# ST_LINK_V2-1.net
KiCad netlist of a schematic drawn in Altium Designer
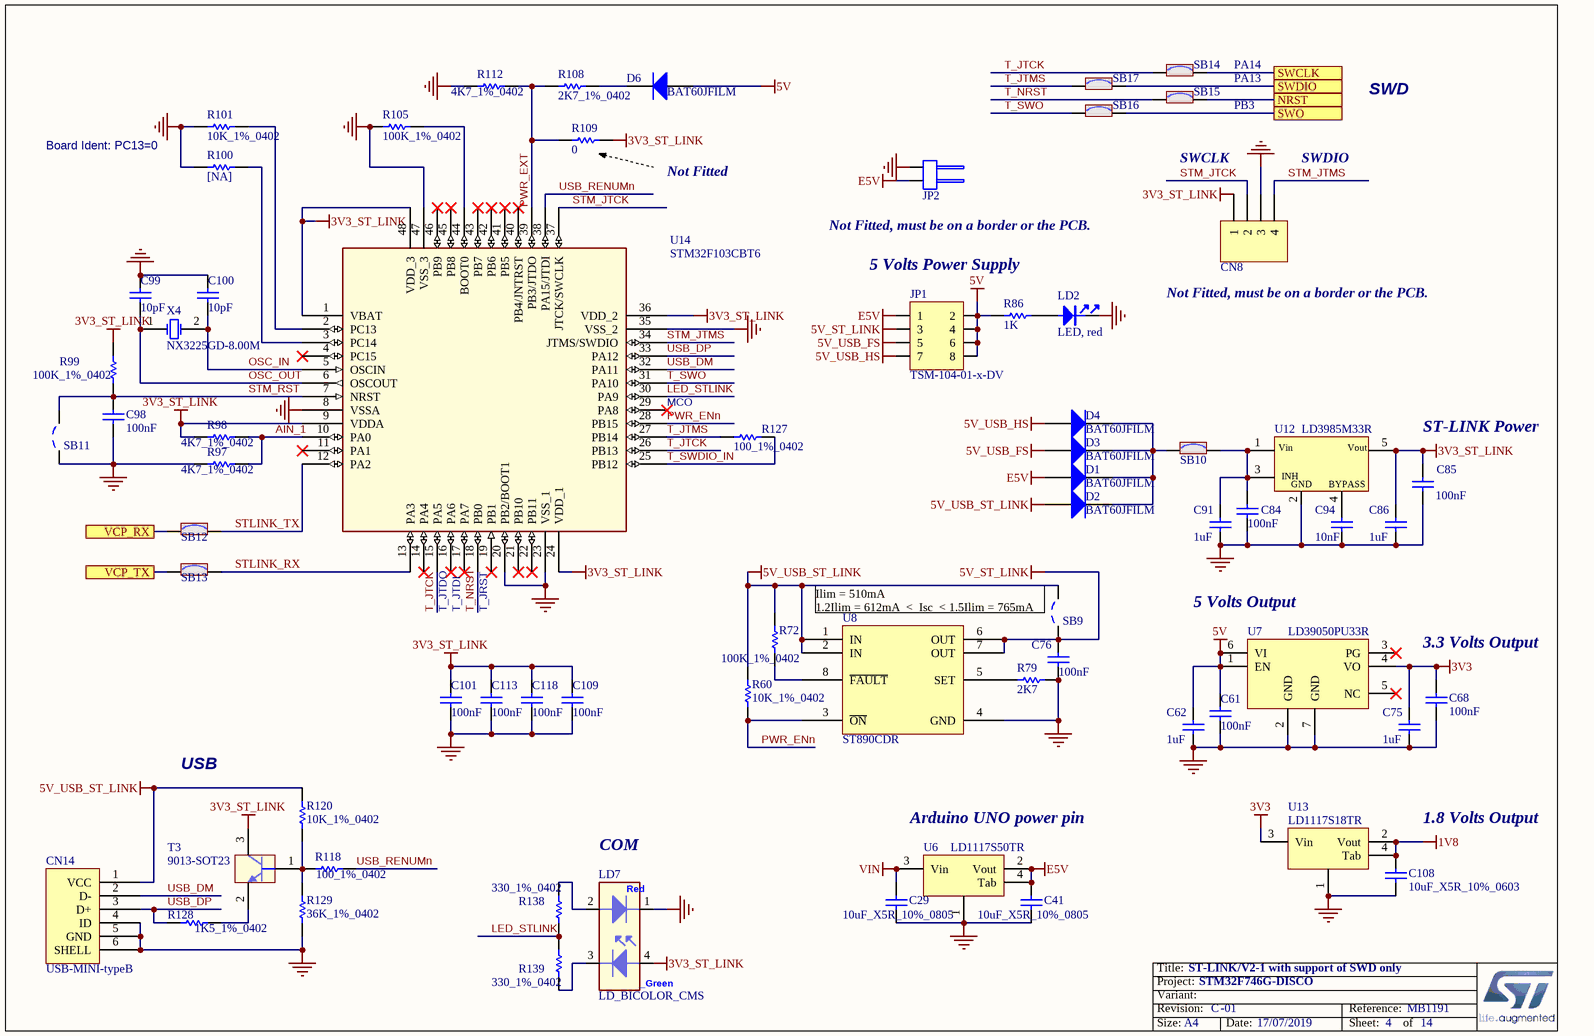
[diagram p0: ST_LINK_V2-1.SCHDOC]

(export (version "E")
  (design (tool "Eeschema 10.0.6"))
  (components
    (comp (ref "C29")
      (value "10uF_X5R_10%_0805")
      (footprint "0805C")
      (description "Capacitor,10uF,25V,X5R,10%,0805,YAGEO")
      (libsource (lib "MCD_TOOLS") (part "Cap_10uF_X5R_10%_0805"))
    )
    (comp (ref "C41")
      (value "10uF_X5R_10%_0805")
      (footprint "0805C")
      (description "Capacitor,10uF,25V,X5R,10%,0805,YAGEO")
      (libsource (lib "MCD_TOOLS") (part "Cap_10uF_X5R_10%_0805"))
    )
    (comp (ref "C61")
      (value "100nF")
      (footprint "0402C")
      (description "Capacitor,100nF,16V,X7R,10%,0402,YAGEO")
      (libsource (lib "MCD_TOOLS") (part "Cap_100nF_X7R_10%_0402"))
    )
    (comp (ref "C62")
      (value "1uF")
      (footprint "0603C")
      (description "Capacitor,1uF,16V,X5R,10%,0603,YAGEO")
      (libsource (lib "MCD_TOOLS") (part "Cap_1uF_X5R_10%_0603"))
    )
    (comp (ref "C68")
      (value "100nF")
      (footprint "0402C")
      (description "Capacitor,100nF,16V,X7R,10%,0402,YAGEO")
      (libsource (lib "MCD_TOOLS") (part "Cap_100nF_X7R_10%_0402"))
    )
    (comp (ref "C75")
      (value "1uF")
      (footprint "0603C")
      (description "Capacitor,1uF,16V,X5R,10%,0603,YAGEO")
      (libsource (lib "MCD_TOOLS") (part "Cap_1uF_X5R_10%_0603"))
    )
    (comp (ref "C76")
      (value "100nF")
      (footprint "0402C")
      (description "Capacitor,100nF,16V,X7R,10%,0402,YAGEO")
      (libsource (lib "MCD_TOOLS") (part "Cap_100nF_X7R_10%_0402"))
    )
    (comp (ref "C84")
      (value "100nF")
      (footprint "0402C")
      (description "Capacitor,100nF,16V,X7R,10%,0402,YAGEO")
      (libsource (lib "MCD_TOOLS") (part "Cap_100nF_X7R_10%_0402"))
    )
    (comp (ref "C85")
      (value "100nF")
      (footprint "0402C")
      (description "Capacitor,100nF,16V,X7R,10%,0402,YAGEO")
      (libsource (lib "MCD_TOOLS") (part "Cap_100nF_X7R_10%_0402"))
    )
    (comp (ref "C86")
      (value "1uF")
      (footprint "0603C")
      (description "Capacitor,1uF,16V,X5R,10%,0603,YAGEO")
      (libsource (lib "MCD_TOOLS") (part "Cap_1uF_X5R_10%_0603"))
    )
    (comp (ref "C91")
      (value "1uF")
      (footprint "0603C")
      (description "Capacitor,1uF,16V,X5R,10%,0603,YAGEO")
      (libsource (lib "MCD_TOOLS") (part "Cap_1uF_X5R_10%_0603"))
    )
    (comp (ref "C94")
      (value "10nF")
      (footprint "0603C")
      (description "Capacitor,10nF,50V,X7R,10%,0603,YAGEO")
      (libsource (lib "MCD_TOOLS") (part "Cap_10nF_X7R_10%_0603"))
    )
    (comp (ref "C98")
      (value "100nF")
      (footprint "0402C")
      (description "Capacitor,100nF,16V,X7R,10%,0402,YAGEO")
      (libsource (lib "MCD_TOOLS") (part "Cap_100nF_X7R_10%_0402"))
    )
    (comp (ref "C99")
      (value "10pF")
      (footprint "0402C")
      (description "Capacitor,10pF,50V,NPO,5%,0402,YAGEO")
      (libsource (lib "MCD_TOOLS") (part "Cap_10pF_NPO_5%_0402"))
    )
    (comp (ref "C100")
      (value "10pF")
      (footprint "0402C")
      (description "Capacitor,10pF,50V,NPO,5%,0402,YAGEO")
      (libsource (lib "MCD_TOOLS") (part "Cap_10pF_NPO_5%_0402"))
    )
    (comp (ref "C101")
      (value "100nF")
      (footprint "0402C")
      (description "Capacitor,100nF,16V,X7R,10%,0402,YAGEO")
      (libsource (lib "MCD_TOOLS") (part "Cap_100nF_X7R_10%_0402"))
    )
    (comp (ref "C108")
      (value "10uF_X5R_10%_0603")
      (footprint "0603C")
      (description "Capacitor,10uF,6.3V,X5R,10%,0603,YAGEO")
      (libsource (lib "MCD_TOOLS") (part "Cap_10uF_X5R_10%_0603"))
    )
    (comp (ref "C109")
      (value "100nF")
      (footprint "0402C")
      (description "Capacitor,100nF,16V,X7R,10%,0402,YAGEO")
      (libsource (lib "MCD_TOOLS") (part "Cap_100nF_X7R_10%_0402"))
    )
    (comp (ref "C113")
      (value "100nF")
      (footprint "0402C")
      (description "Capacitor,100nF,16V,X7R,10%,0402,YAGEO")
      (libsource (lib "MCD_TOOLS") (part "Cap_100nF_X7R_10%_0402"))
    )
    (comp (ref "C118")
      (value "100nF")
      (footprint "0402C")
      (description "Capacitor,100nF,16V,X7R,10%,0402,YAGEO")
      (libsource (lib "MCD_TOOLS") (part "Cap_100nF_X7R_10%_0402"))
    )
    (comp (ref "CN8")
      (value "Header 4")
      (footprint "Header 4")
      (description "Header, 4-Pin")
      (fields (field (name "PUBLISHER") "Altium Limited"))
      (libsource (lib "MCD_TOOLS") (part "Header 4"))
    )
    (comp (ref "CN14")
      (value "USB-MINI-typeB")
      (footprint "USB-MINI-B-SMD")
      (description "USB-MINI-typeB connector")
      (libsource (lib "MCD_TOOLS") (part "USB-MINI-typeB connector"))
    )
    (comp (ref "D1")
      (value "BAT60JFILM")
      (footprint "SOD323/A")
      (libsource (lib "MCD_TOOLS") (part "BAT60JFILM"))
    )
    (comp (ref "D2")
      (value "BAT60JFILM")
      (footprint "SOD323/A")
      (libsource (lib "MCD_TOOLS") (part "BAT60JFILM"))
    )
    (comp (ref "D3")
      (value "BAT60JFILM")
      (footprint "SOD323/A")
      (libsource (lib "MCD_TOOLS") (part "BAT60JFILM"))
    )
    (comp (ref "D4")
      (value "BAT60JFILM")
      (footprint "SOD323/A")
      (libsource (lib "MCD_TOOLS") (part "BAT60JFILM"))
    )
    (comp (ref "D6")
      (value "BAT60JFILM")
      (footprint "SOD323/A")
      (libsource (lib "MCD_TOOLS") (part "BAT60JFILM"))
    )
    (comp (ref "JP1")
      (value "TSM-104-01-x-DV")
      (footprint "TSM-104-01-x-DV")
      (description "Header, 4-Pins, Double row Vertical, SMD, 2.54")
      (libsource (lib "MCD_TOOLS") (part "Header_4X2_SMD"))
    )
    (comp (ref "JP2")
      (value "TSM-102-01-F-SH-A")
      (footprint "TSM-102-01-F-SH-A")
      (description "Header, 2-Pins, Single row Horizontal SMD, 2.54")
      (libsource (lib "MCD_TOOLS") (part "JP2_CMS"))
    )
    (comp (ref "LD2")
      (value "LED, red")
      (footprint "0603D")
      (description "LED, red, 0603")
      (libsource (lib "MCD_TOOLS") (part "LED_red"))
    )
    (comp (ref "LD7")
      (value "LD_BICOLOR_CMS")
      (footprint "HSMF-A201")
      (description "Bicolor Led")
      (libsource (lib "MCD_TOOLS") (part "LD_BICOLOR_CMS"))
    )
    (comp (ref "R60")
      (value "10K_1%_0402")
      (footprint "0402R")
      (description "Resistor,10K,0402,1%,YAGEO")
      (libsource (lib "MCD_TOOLS") (part "Res_10K_1%_0402"))
    )
    (comp (ref "R72")
      (value "100K_1%_0402")
      (footprint "0402R")
      (description "Resistor,100K,0402,1%,YAGEO")
      (libsource (lib "MCD_TOOLS") (part "Res_100K_1%_0402"))
    )
    (comp (ref "R79")
      (value "2K7")
      (footprint "0402R")
      (description "Resistor,2K7,0402,1%,YAGEO")
      (libsource (lib "MCD_TOOLS") (part "Res_2K7_1%_0402"))
    )
    (comp (ref "R86")
      (value "1K")
      (footprint "0402R")
      (description "Resistor,1K,0402,1%,YAGEO")
      (libsource (lib "MCD_TOOLS") (part "Res_1K_1%_0402"))
    )
    (comp (ref "R97")
      (value "4K7_1%_0402")
      (footprint "0402R")
      (description "Resistor,4K7,0402,1%,YAGEO")
      (libsource (lib "MCD_TOOLS") (part "Res_4K7_1%_0402"))
    )
    (comp (ref "R98")
      (value "4K7_1%_0402")
      (footprint "0402R")
      (description "Resistor,4K7,0402,1%,YAGEO")
      (libsource (lib "MCD_TOOLS") (part "Res_4K7_1%_0402"))
    )
    (comp (ref "R99")
      (value "100K_1%_0402")
      (footprint "0402R")
      (description "Resistor,100K,0402,1%,YAGEO")
      (libsource (lib "MCD_TOOLS") (part "Res_100K_1%_0402"))
    )
    (comp (ref "R100")
      (value "[NA]")
      (footprint "0402R")
      (description "Resistor,[NA],0402")
      (libsource (lib "MCD_TOOLS") (part "Res_NA_0402"))
    )
    (comp (ref "R101")
      (value "10K_1%_0402")
      (footprint "0402R")
      (description "Resistor,10K,0402,1%,YAGEO")
      (libsource (lib "MCD_TOOLS") (part "Res_10K_1%_0402"))
    )
    (comp (ref "R105")
      (value "100K_1%_0402")
      (footprint "0402R")
      (description "Resistor,100K,0402,1%,YAGEO")
      (libsource (lib "MCD_TOOLS") (part "Res_100K_1%_0402"))
    )
    (comp (ref "R108")
      (value "2K7_1%_0402")
      (footprint "0402R")
      (description "Resistor,2K7,0402,1%,YAGEO")
      (libsource (lib "MCD_TOOLS") (part "Res_2K7_1%_0402"))
    )
    (comp (ref "R109")
      (value "0")
      (footprint "0402R")
      (description "Resistor,0,0402,5%,YAGEO")
      (libsource (lib "MCD_TOOLS") (part "Res_0_5%_0402"))
    )
    (comp (ref "R112")
      (value "4K7_1%_0402")
      (footprint "0402R")
      (description "Resistor,4K7,0402,1%,YAGEO")
      (libsource (lib "MCD_TOOLS") (part "Res_4K7_1%_0402"))
    )
    (comp (ref "R118")
      (value "100_1%_0402")
      (footprint "0402R")
      (description "Resistor,100,0402,1%,YAGEO")
      (libsource (lib "MCD_TOOLS") (part "Res_100_1%_0402"))
    )
    (comp (ref "R120")
      (value "10K_1%_0402")
      (footprint "0402R")
      (description "Resistor,10K,0402,1%,YAGEO")
      (libsource (lib "MCD_TOOLS") (part "Res_10K_1%_0402"))
    )
    (comp (ref "R127")
      (value "100_1%_0402")
      (footprint "0402R")
      (description "Resistor,100,0402,1%,YAGEO")
      (libsource (lib "MCD_TOOLS") (part "Res_100_1%_0402"))
    )
    (comp (ref "R128")
      (value "1K5_1%_0402")
      (footprint "0402R")
      (description "Resistor,1K5,0402,1%,YAGEO")
      (libsource (lib "MCD_TOOLS") (part "Res_1K5_1%_0402"))
    )
    (comp (ref "R129")
      (value "36K_1%_0402")
      (footprint "0402R")
      (description "Resistor,36K,0402,1%,YAGEO")
      (libsource (lib "MCD_TOOLS") (part "Res_36K_1%_0402"))
    )
    (comp (ref "R138")
      (value "330_1%_0402")
      (footprint "0402R")
      (description "Resistor,330,0402,1%,YAGEO")
      (libsource (lib "MCD_TOOLS") (part "Res_330_1%_0402"))
    )
    (comp (ref "R139")
      (value "330_1%_0402")
      (footprint "0402R")
      (description "Resistor,330,0402,1%,YAGEO")
      (libsource (lib "MCD_TOOLS") (part "Res_330_1%_0402"))
    )
    (comp (ref "SB9")
      (value "Solder Bridge OFF")
      (footprint "JP2_SMD")
      (libsource (lib "MCD_TOOLS") (part "SB_OFF"))
    )
    (comp (ref "SB10")
      (value "Solder Bridge ON")
      (footprint "JP2_SMD")
      (libsource (lib "MCD_TOOLS") (part "SB_ON"))
    )
    (comp (ref "SB11")
      (value "Solder Bridge OFF")
      (footprint "JP2_SMD")
      (libsource (lib "MCD_TOOLS") (part "SB_OFF"))
    )
    (comp (ref "SB12")
      (value "Solder Bridge ON")
      (footprint "JP2_SMD")
      (libsource (lib "MCD_TOOLS") (part "SB_ON"))
    )
    (comp (ref "SB13")
      (value "Solder Bridge ON")
      (footprint "JP2_SMD")
      (libsource (lib "MCD_TOOLS") (part "SB_ON"))
    )
    (comp (ref "SB14")
      (value "Solder Bridge ON")
      (footprint "JP2_SMD")
      (libsource (lib "MCD_TOOLS") (part "SB_ON"))
    )
    (comp (ref "SB15")
      (value "Solder Bridge ON")
      (footprint "JP2_SMD")
      (libsource (lib "MCD_TOOLS") (part "SB_ON"))
    )
    (comp (ref "SB16")
      (value "Solder Bridge ON")
      (footprint "JP2_SMD")
      (libsource (lib "MCD_TOOLS") (part "SB_ON"))
    )
    (comp (ref "SB17")
      (value "Solder Bridge ON")
      (footprint "JP2_SMD")
      (libsource (lib "MCD_TOOLS") (part "SB_ON"))
    )
    (comp (ref "T3")
      (value "9013-SOT23")
      (footprint "SOT23")
      (description "NPN Bipolar Transistor")
      (libsource (lib "MCD_TOOLS") (part "9013-SOT23"))
    )
    (comp (ref "U6")
      (value "LD1117S50TR")
      (footprint "SOT-223")
      (description "IC REG LDO 5V 0.8A SOT223")
      (libsource (lib "MCD_TOOLS") (part "LD1117S50TR"))
    )
    (comp (ref "U7")
      (value "LD39050PU33R")
      (footprint "DFN6_3x3")
      (description "Ultra low drop-low , 500 mA low quiescent current")
      (libsource (lib "MCD_TOOLS") (part "LD39050P"))
    )
    (comp (ref "U8")
      (value "ST890CDR")
      (footprint "SO-8")
      (description "1.2 A current limited high-side power switch with thermal shutdown")
      (libsource (lib "MCD_TOOLS") (part "ST890CDR"))
    )
    (comp (ref "U12")
      (value "LD3985M33R")
      (footprint "SOT23-5L")
      (description "Ultra low drop-low noise BiCMOS voltage, regulators low ESR capacitors compatible")
      (libsource (lib "MCD_TOOLS") (part "LD3985M33R"))
    )
    (comp (ref "U13")
      (value "LD1117S18TR")
      (footprint "SOT-223")
      (description "LOW DROP FIXED AND ADJUSTABLE POSITIVE VOLTAGE REGULATORS (1.8 Volts)")
      (libsource (lib "MCD_TOOLS") (part "LD1117S18TR"))
    )
    (comp (ref "U14")
      (value "STM32F103CBT6")
      (footprint "QFP48 7x7")
      (description "Medium-density performance line ARM-based 32-bit MCU with 128KB Flash")
      (libsource (lib "MCD_TOOLS") (part "STM32F103CBT6"))
    )
    (comp (ref "X4")
      (value "NX3225GD-8.00M")
      (footprint "XTAL_2SM_3R2X2R5")
      (description "Crystal 8Mhz, 8pF, -+50PPM, SMD")
      (libsource (lib "MCD_TOOLS") (part "XTAL_8M_NX3225GD"))
    )
  )
  (nets
    (net (code "1") (name "/AIN_1") (class "Default")
      (node (ref "R97") (pin "2") (pinfunction "2_2") (pintype "passive"))
      (node (ref "R98") (pin "2") (pinfunction "2_2") (pintype "passive"))
      (node (ref "U14") (pin "10") (pinfunction "PA0_10") (pintype "bidirectional"))
    )
    (net (code "2") (name "/LED_STLINK") (class "Default")
      (node (ref "R138") (pin "1") (pinfunction "1_1") (pintype "passive"))
      (node (ref "R139") (pin "2") (pinfunction "2_2") (pintype "passive"))
      (node (ref "U14") (pin "30") (pinfunction "PA9_30") (pintype "bidirectional"))
    )
    (net (code "3") (name "/NRST") (class "Default")
      (node (ref "SB15") (pin "2") (pinfunction "2_2") (pintype "passive"))
    )
    (net (code "4") (name "/OSC_IN") (class "Default")
      (node (ref "C100") (pin "2") (pinfunction "2_2") (pintype "passive"))
      (node (ref "U14") (pin "5") (pinfunction "OSCIN_5") (pintype "input"))
      (node (ref "X4") (pin "2") (pinfunction "OSC2_2") (pintype "passive"))
    )
    (net (code "5") (name "/OSC_OUT") (class "Default")
      (node (ref "C99") (pin "2") (pinfunction "2_2") (pintype "passive"))
      (node (ref "U14") (pin "6") (pinfunction "OSCOUT_6") (pintype "output"))
      (node (ref "X4") (pin "1") (pinfunction "OSC1_1") (pintype "passive"))
    )
    (net (code "6") (name "/PWR_ENn") (class "Default")
      (node (ref "R60") (pin "1") (pinfunction "1_1") (pintype "passive"))
      (node (ref "U14") (pin "28") (pinfunction "PB15_28") (pintype "bidirectional"))
      (node (ref "U8") (pin "3") (pinfunction "~{ON}_3") (pintype "passive"))
    )
    (net (code "7") (name "/PWR_EXT") (class "Default")
      (node (ref "R108") (pin "1") (pinfunction "1_1") (pintype "passive"))
      (node (ref "R109") (pin "1") (pinfunction "1_1") (pintype "passive"))
      (node (ref "R112") (pin "2") (pinfunction "2_2") (pintype "passive"))
      (node (ref "U14") (pin "39") (pinfunction "PB3/JTDO_39") (pintype "bidirectional"))
    )
    (net (code "8") (name "/STLINK_RX") (class "Default")
      (node (ref "SB13") (pin "2") (pinfunction "2_2") (pintype "passive"))
      (node (ref "U14") (pin "13") (pinfunction "PA3_13") (pintype "bidirectional"))
    )
    (net (code "9") (name "/STLINK_TX") (class "Default")
      (node (ref "SB12") (pin "2") (pinfunction "2_2") (pintype "passive"))
      (node (ref "U14") (pin "12") (pinfunction "PA2_12") (pintype "bidirectional"))
    )
    (net (code "10") (name "/STM_JTCK") (class "Default")
      (node (ref "CN8") (pin "2") (pinfunction "2_2") (pintype "passive"))
      (node (ref "U14") (pin "37") (pinfunction "JTCK/SWCLK_37") (pintype "bidirectional"))
    )
    (net (code "11") (name "/STM_JTMS") (class "Default")
      (node (ref "CN8") (pin "4") (pinfunction "4_4") (pintype "passive"))
      (node (ref "U14") (pin "34") (pinfunction "JTMS/SWDIO_34") (pintype "bidirectional"))
    )
    (net (code "12") (name "/STM_RST") (class "Default")
      (node (ref "C98") (pin "2") (pinfunction "2_2") (pintype "passive"))
      (node (ref "R99") (pin "1") (pinfunction "1_1") (pintype "passive"))
      (node (ref "SB11") (pin "2") (pinfunction "2_2") (pintype "passive"))
      (node (ref "U14") (pin "7") (pinfunction "NRST_7") (pintype "input"))
    )
    (net (code "13") (name "/SWCLK") (class "Default")
      (node (ref "SB14") (pin "2") (pinfunction "2_2") (pintype "passive"))
    )
    (net (code "14") (name "/SWDIO") (class "Default")
      (node (ref "SB17") (pin "2") (pinfunction "2_2") (pintype "passive"))
    )
    (net (code "15") (name "/SWO") (class "Default")
      (node (ref "SB16") (pin "2") (pinfunction "2_2") (pintype "passive"))
    )
    (net (code "16") (name "/T_JTCK") (class "Default")
      (node (ref "SB14") (pin "1") (pinfunction "1_1") (pintype "passive"))
      (node (ref "U14") (pin "15") (pinfunction "PA5_15") (pintype "bidirectional"))
      (node (ref "U14") (pin "26") (pinfunction "PB13_26") (pintype "bidirectional"))
    )
    (net (code "17") (name "/T_JTMS") (class "Default")
      (node (ref "R127") (pin "1") (pinfunction "1_1") (pintype "passive"))
      (node (ref "SB17") (pin "1") (pinfunction "1_1") (pintype "passive"))
      (node (ref "U14") (pin "27") (pinfunction "PB14_27") (pintype "bidirectional"))
    )
    (net (code "18") (name "/T_NRST") (class "Default")
      (node (ref "SB15") (pin "1") (pinfunction "1_1") (pintype "passive"))
      (node (ref "U14") (pin "18") (pinfunction "PB0_18") (pintype "bidirectional"))
    )
    (net (code "19") (name "/T_SWDIO_IN") (class "Default")
      (node (ref "R127") (pin "2") (pinfunction "2_2") (pintype "passive"))
      (node (ref "U14") (pin "25") (pinfunction "PB12_25") (pintype "bidirectional"))
    )
    (net (code "20") (name "/T_SWO") (class "Default")
      (node (ref "SB16") (pin "1") (pinfunction "1_1") (pintype "passive"))
      (node (ref "U14") (pin "31") (pinfunction "PA10_31") (pintype "bidirectional"))
    )
    (net (code "21") (name "/USB_DM") (class "Default")
      (node (ref "CN14") (pin "2") (pinfunction "D-_2") (pintype "passive"))
      (node (ref "U14") (pin "32") (pinfunction "PA11_32") (pintype "bidirectional"))
    )
    (net (code "22") (name "/USB_DP") (class "Default")
      (node (ref "CN14") (pin "3") (pinfunction "D+_3") (pintype "passive"))
      (node (ref "R128") (pin "1") (pinfunction "1_1") (pintype "passive"))
      (node (ref "U14") (pin "33") (pinfunction "PA12_33") (pintype "bidirectional"))
    )
    (net (code "23") (name "/USB_RENUMn") (class "Default")
      (node (ref "R118") (pin "2") (pinfunction "2_2") (pintype "passive"))
      (node (ref "U14") (pin "38") (pinfunction "PA15/JTDI_38") (pintype "bidirectional"))
    )
    (net (code "24") (name "/VCP_RX") (class "Default")
      (node (ref "SB12") (pin "1") (pinfunction "1_1") (pintype "passive"))
    )
    (net (code "25") (name "/VCP_TX") (class "Default")
      (node (ref "SB13") (pin "1") (pinfunction "1_1") (pintype "passive"))
    )
    (net (code "26") (name "1V8") (class "Default")
      (node (ref "C108") (pin "2") (pinfunction "2_2") (pintype "passive"))
      (node (ref "U13") (pin "2") (pinfunction "Vout_2") (pintype "passive"))
      (node (ref "U13") (pin "4") (pinfunction "Tab_4") (pintype "passive"))
    )
    (net (code "27") (name "3V3") (class "Default")
      (node (ref "C68") (pin "2") (pinfunction "2_2") (pintype "passive"))
      (node (ref "C75") (pin "2") (pinfunction "2_2") (pintype "passive"))
      (node (ref "U13") (pin "3") (pinfunction "Vin_3") (pintype "passive"))
      (node (ref "U7") (pin "4") (pinfunction "VO_4") (pintype "passive"))
    )
    (net (code "28") (name "3V3_ST_LINK") (class "Default")
      (node (ref "C101") (pin "2") (pinfunction "2_2") (pintype "passive"))
      (node (ref "C109") (pin "2") (pinfunction "2_2") (pintype "passive"))
      (node (ref "C113") (pin "2") (pinfunction "2_2") (pintype "passive"))
      (node (ref "C118") (pin "1") (pinfunction "1_1") (pintype "passive"))
      (node (ref "C85") (pin "2") (pinfunction "2_2") (pintype "passive"))
      (node (ref "C86") (pin "1") (pinfunction "1_1") (pintype "passive"))
      (node (ref "CN8") (pin "1") (pinfunction "1_1") (pintype "passive"))
      (node (ref "LD7") (pin "4") (pinfunction "4_4") (pintype "passive"))
      (node (ref "R109") (pin "2") (pinfunction "2_2") (pintype "passive"))
      (node (ref "R98") (pin "1") (pinfunction "1_1") (pintype "passive"))
      (node (ref "R99") (pin "2") (pinfunction "2_2") (pintype "passive"))
      (node (ref "T3") (pin "3") (pinfunction "C_3") (pintype "passive"))
      (node (ref "U12") (pin "5") (pinfunction "Vout_5") (pintype "passive"))
      (node (ref "U14") (pin "1") (pinfunction "VBAT_1") (pintype "power_in"))
      (node (ref "U14") (pin "24") (pinfunction "VDD_1_24") (pintype "power_in"))
      (node (ref "U14") (pin "36") (pinfunction "VDD_2_36") (pintype "power_in"))
      (node (ref "U14") (pin "48") (pinfunction "VDD_3_48") (pintype "power_in"))
      (node (ref "U14") (pin "9") (pinfunction "VDDA_9") (pintype "power_in"))
    )
    (net (code "29") (name "5V") (class "Default")
      (node (ref "C61") (pin "2") (pinfunction "2_2") (pintype "passive"))
      (node (ref "C62") (pin "2") (pinfunction "2_2") (pintype "passive"))
      (node (ref "D6") (pin "1") (pinfunction "A_1") (pintype "passive"))
      (node (ref "JP1") (pin "2") (pinfunction "2_2") (pintype "passive"))
      (node (ref "JP1") (pin "4") (pinfunction "4_4") (pintype "passive"))
      (node (ref "JP1") (pin "6") (pinfunction "6_6") (pintype "passive"))
      (node (ref "JP1") (pin "8") (pinfunction "8_8") (pintype "passive"))
      (node (ref "R86") (pin "1") (pinfunction "1_1") (pintype "passive"))
      (node (ref "U7") (pin "1") (pinfunction "EN_1") (pintype "passive"))
      (node (ref "U7") (pin "6") (pinfunction "VI_6") (pintype "passive"))
    )
    (net (code "30") (name "5V_ST_LINK") (class "Default")
      (node (ref "C76") (pin "2") (pinfunction "2_2") (pintype "passive"))
      (node (ref "JP1") (pin "3") (pinfunction "3_3") (pintype "passive"))
      (node (ref "SB9") (pin "1") (pinfunction "1_1") (pintype "passive"))
      (node (ref "U8") (pin "6") (pinfunction "OUT_6") (pintype "passive"))
      (node (ref "U8") (pin "7") (pinfunction "OUT_7") (pintype "passive"))
    )
    (net (code "31") (name "5V_USB_FS") (class "Default")
      (node (ref "D3") (pin "1") (pinfunction "A_1") (pintype "passive"))
      (node (ref "JP1") (pin "5") (pinfunction "5_5") (pintype "passive"))
    )
    (net (code "32") (name "5V_USB_HS") (class "Default")
      (node (ref "D4") (pin "1") (pinfunction "A_1") (pintype "passive"))
      (node (ref "JP1") (pin "7") (pinfunction "7_7") (pintype "passive"))
    )
    (net (code "33") (name "5V_USB_ST_LINK") (class "Default")
      (node (ref "CN14") (pin "1") (pinfunction "VCC_1") (pintype "power_in"))
      (node (ref "D2") (pin "1") (pinfunction "A_1") (pintype "passive"))
      (node (ref "R120") (pin "2") (pinfunction "2_2") (pintype "passive"))
      (node (ref "R60") (pin "2") (pinfunction "2_2") (pintype "passive"))
      (node (ref "R72") (pin "2") (pinfunction "2_2") (pintype "passive"))
      (node (ref "SB9") (pin "2") (pinfunction "2_2") (pintype "passive"))
      (node (ref "U8") (pin "1") (pinfunction "IN_1") (pintype "passive"))
      (node (ref "U8") (pin "2") (pinfunction "IN_2") (pintype "passive"))
    )
    (net (code "34") (name "E5V") (class "Default")
      (node (ref "C41") (pin "2") (pinfunction "2_2") (pintype "passive"))
      (node (ref "D1") (pin "1") (pinfunction "A_1") (pintype "passive"))
      (node (ref "JP1") (pin "1") (pinfunction "1_1") (pintype "passive"))
      (node (ref "JP2") (pin "2") (pinfunction "NO_2") (pintype "passive"))
      (node (ref "U6") (pin "2") (pinfunction "Vout_2") (pintype "passive"))
      (node (ref "U6") (pin "4") (pinfunction "Tab_4") (pintype "passive"))
    )
    (net (code "35") (name "GND") (class "Default")
      (node (ref "C100") (pin "1") (pinfunction "1_1") (pintype "passive"))
      (node (ref "C101") (pin "1") (pinfunction "1_1") (pintype "passive"))
      (node (ref "C108") (pin "1") (pinfunction "1_1") (pintype "passive"))
      (node (ref "C109") (pin "1") (pinfunction "1_1") (pintype "passive"))
      (node (ref "C113") (pin "1") (pinfunction "1_1") (pintype "passive"))
      (node (ref "C118") (pin "2") (pinfunction "2_2") (pintype "passive"))
      (node (ref "C29") (pin "1") (pinfunction "1_1") (pintype "passive"))
      (node (ref "C41") (pin "1") (pinfunction "1_1") (pintype "passive"))
      (node (ref "C61") (pin "1") (pinfunction "1_1") (pintype "passive"))
      (node (ref "C62") (pin "1") (pinfunction "1_1") (pintype "passive"))
      (node (ref "C68") (pin "1") (pinfunction "1_1") (pintype "passive"))
      (node (ref "C75") (pin "1") (pinfunction "1_1") (pintype "passive"))
      (node (ref "C76") (pin "1") (pinfunction "1_1") (pintype "passive"))
      (node (ref "C84") (pin "1") (pinfunction "1_1") (pintype "passive"))
      (node (ref "C85") (pin "1") (pinfunction "1_1") (pintype "passive"))
      (node (ref "C86") (pin "2") (pinfunction "2_2") (pintype "passive"))
      (node (ref "C91") (pin "1") (pinfunction "1_1") (pintype "passive"))
      (node (ref "C94") (pin "1") (pinfunction "1_1") (pintype "passive"))
      (node (ref "C98") (pin "1") (pinfunction "1_1") (pintype "passive"))
      (node (ref "C99") (pin "1") (pinfunction "1_1") (pintype "passive"))
      (node (ref "CN14") (pin "4") (pinfunction "ID_4") (pintype "passive"))
      (node (ref "CN14") (pin "5") (pinfunction "GND_5") (pintype "passive"))
      (node (ref "CN14") (pin "6") (pinfunction "SHELL_6") (pintype "passive"))
      (node (ref "CN8") (pin "3") (pinfunction "3_3") (pintype "passive"))
      (node (ref "JP2") (pin "1") (pinfunction "COMMON_1") (pintype "passive"))
      (node (ref "LD2") (pin "2") (pintype "passive"))
      (node (ref "LD7") (pin "1") (pinfunction "1_1") (pintype "passive"))
      (node (ref "R100") (pin "1") (pinfunction "1_1") (pintype "passive"))
      (node (ref "R101") (pin "1") (pinfunction "1_1") (pintype "passive"))
      (node (ref "R105") (pin "1") (pinfunction "1_1") (pintype "passive"))
      (node (ref "R112") (pin "1") (pinfunction "1_1") (pintype "passive"))
      (node (ref "R129") (pin "1") (pinfunction "1_1") (pintype "passive"))
      (node (ref "R79") (pin "2") (pinfunction "2_2") (pintype "passive"))
      (node (ref "R97") (pin "1") (pinfunction "1_1") (pintype "passive"))
      (node (ref "SB11") (pin "1") (pinfunction "1_1") (pintype "passive"))
      (node (ref "U12") (pin "2") (pinfunction "GND_2") (pintype "passive"))
      (node (ref "U13") (pin "1") (pintype "passive"))
      (node (ref "U14") (pin "20") (pinfunction "PB2/BOOT1_20") (pintype "bidirectional"))
      (node (ref "U14") (pin "23") (pinfunction "VSS_1_23") (pintype "power_in"))
      (node (ref "U14") (pin "35") (pinfunction "VSS_2_35") (pintype "power_in"))
      (node (ref "U14") (pin "47") (pinfunction "VSS_3_47") (pintype "power_in"))
      (node (ref "U14") (pin "8") (pinfunction "VSSA_8") (pintype "power_in"))
      (node (ref "U6") (pin "1") (pintype "passive"))
      (node (ref "U7") (pin "2") (pinfunction "GND_2") (pintype "passive"))
      (node (ref "U7") (pin "7") (pinfunction "GND_7") (pintype "passive"))
      (node (ref "U8") (pin "4") (pinfunction "GND_4") (pintype "passive"))
    )
    (net (code "36") (name "Net-(D1-K)") (class "Default")
      (node (ref "D1") (pin "2") (pinfunction "K_2") (pintype "passive"))
      (node (ref "D2") (pin "2") (pinfunction "K_2") (pintype "passive"))
      (node (ref "D3") (pin "2") (pinfunction "K_2") (pintype "passive"))
      (node (ref "D4") (pin "2") (pinfunction "K_2") (pintype "passive"))
      (node (ref "SB10") (pin "1") (pinfunction "1_1") (pintype "passive"))
    )
    (net (code "37") (name "Net-(D6-K)") (class "Default")
      (node (ref "D6") (pin "2") (pinfunction "K_2") (pintype "passive"))
      (node (ref "R108") (pin "2") (pinfunction "2_2") (pintype "passive"))
    )
    (net (code "38") (name "Net-(LD2-Pad1)") (class "Default")
      (node (ref "LD2") (pin "1") (pintype "passive"))
      (node (ref "R86") (pin "2") (pinfunction "2_2") (pintype "passive"))
    )
    (net (code "39") (name "Net-(LD7-Pad2)") (class "Default")
      (node (ref "LD7") (pin "2") (pinfunction "2_2") (pintype "passive"))
      (node (ref "R138") (pin "2") (pinfunction "2_2") (pintype "passive"))
    )
    (net (code "40") (name "Net-(LD7-Pad3)") (class "Default")
      (node (ref "LD7") (pin "3") (pinfunction "3_3") (pintype "passive"))
      (node (ref "R139") (pin "1") (pinfunction "1_1") (pintype "passive"))
    )
    (net (code "41") (name "Net-(T3-B)") (class "Default")
      (node (ref "R118") (pin "1") (pinfunction "1_1") (pintype "passive"))
      (node (ref "R120") (pin "1") (pinfunction "1_1") (pintype "passive"))
      (node (ref "R129") (pin "2") (pinfunction "2_2") (pintype "passive"))
      (node (ref "T3") (pin "1") (pinfunction "B_1") (pintype "passive"))
    )
    (net (code "42") (name "Net-(T3-E)") (class "Default")
      (node (ref "R128") (pin "2") (pinfunction "2_2") (pintype "passive"))
      (node (ref "T3") (pin "2") (pinfunction "E_2") (pintype "passive"))
    )
    (net (code "43") (name "Net-(U8-SET)") (class "Default")
      (node (ref "R79") (pin "1") (pinfunction "1_1") (pintype "passive"))
      (node (ref "U8") (pin "5") (pinfunction "SET_5") (pintype "passive"))
    )
    (net (code "44") (name "Net-(U8-~{FAULT})") (class "Default")
      (node (ref "R72") (pin "1") (pinfunction "1_1") (pintype "passive"))
      (node (ref "U8") (pin "8") (pinfunction "~{FAULT}_8") (pintype "passive"))
    )
    (net (code "45") (name "Net-(U12-BYPASS)") (class "Default")
      (node (ref "C94") (pin "2") (pinfunction "2_2") (pintype "passive"))
      (node (ref "U12") (pin "4") (pinfunction "BYPASS_4") (pintype "passive"))
    )
    (net (code "46") (name "Net-(U12-CE)") (class "Default")
      (node (ref "C84") (pin "2") (pinfunction "2_2") (pintype "passive"))
      (node (ref "C91") (pin "2") (pinfunction "2_2") (pintype "passive"))
      (node (ref "SB10") (pin "2") (pinfunction "2_2") (pintype "passive"))
      (node (ref "U12") (pin "1") (pinfunction "Vin_1") (pintype "passive"))
      (node (ref "U12") (pin "3") (pinfunction "CE_3") (pintype "passive"))
    )
    (net (code "47") (name "Net-(U14-BOOT0)") (class "Default")
      (node (ref "R105") (pin "2") (pinfunction "2_2") (pintype "passive"))
      (node (ref "U14") (pin "44") (pinfunction "BOOT0_44") (pintype "bidirectional"))
    )
    (net (code "48") (name "Net-(U14-PC13)") (class "Default")
      (node (ref "R101") (pin "2") (pinfunction "2_2") (pintype "passive"))
      (node (ref "U14") (pin "2") (pinfunction "PC13_2") (pintype "bidirectional"))
    )
    (net (code "49") (name "Net-(U14-PC14)") (class "Default")
      (node (ref "R100") (pin "2") (pinfunction "2_2") (pintype "passive"))
      (node (ref "U14") (pin "3") (pinfunction "PC14_3") (pintype "bidirectional"))
    )
    (net (code "50") (name "VIN") (class "Default")
      (node (ref "C29") (pin "2") (pinfunction "2_2") (pintype "passive"))
      (node (ref "U6") (pin "3") (pinfunction "Vin_3") (pintype "passive"))
    )
    (net (code "51") (name "unconnected-(U7-NC-Pad5)") (class "Default")
      (node (ref "U7") (pin "5") (pinfunction "NC_5") (pintype "passive+no_connect"))
    )
    (net (code "52") (name "unconnected-(U7-PG-Pad3)") (class "Default")
      (node (ref "U7") (pin "3") (pinfunction "PG_3") (pintype "passive+no_connect"))
    )
    (net (code "53") (name "unconnected-(U14-PA1-Pad11)") (class "Default")
      (node (ref "U14") (pin "11") (pinfunction "PA1_11") (pintype "bidirectional+no_connect"))
    )
    (net (code "54") (name "unconnected-(U14-PA4-Pad14)") (class "Default")
      (node (ref "U14") (pin "14") (pinfunction "PA4_14") (pintype "bidirectional+no_connect"))
    )
    (net (code "55") (name "unconnected-(U14-PA6-Pad16)") (class "Default")
      (node (ref "U14") (pin "16") (pinfunction "PA6_16") (pintype "bidirectional+no_connect"))
    )
    (net (code "56") (name "unconnected-(U14-PA7-Pad17)") (class "Default")
      (node (ref "U14") (pin "17") (pinfunction "PA7_17") (pintype "bidirectional+no_connect"))
    )
    (net (code "57") (name "unconnected-(U14-PA8-Pad29)") (class "Default")
      (node (ref "U14") (pin "29") (pinfunction "PA8_29") (pintype "bidirectional+no_connect"))
    )
    (net (code "58") (name "unconnected-(U14-PB1-Pad19)") (class "Default")
      (node (ref "U14") (pin "19") (pinfunction "PB1_19") (pintype "input+no_connect"))
    )
    (net (code "59") (name "unconnected-(U14-PB4{slash}JNTRST-Pad40)") (class "Default")
      (node (ref "U14") (pin "40") (pinfunction "PB4/JNTRST_40") (pintype "bidirectional+no_connect"))
    )
    (net (code "60") (name "unconnected-(U14-PB5-Pad41)") (class "Default")
      (node (ref "U14") (pin "41") (pinfunction "PB5_41") (pintype "bidirectional+no_connect"))
    )
    (net (code "61") (name "unconnected-(U14-PB6-Pad42)") (class "Default")
      (node (ref "U14") (pin "42") (pinfunction "PB6_42") (pintype "bidirectional+no_connect"))
    )
    (net (code "62") (name "unconnected-(U14-PB7-Pad43)") (class "Default")
      (node (ref "U14") (pin "43") (pinfunction "PB7_43") (pintype "bidirectional+no_connect"))
    )
    (net (code "63") (name "unconnected-(U14-PB8-Pad45)") (class "Default")
      (node (ref "U14") (pin "45") (pinfunction "PB8_45") (pintype "bidirectional+no_connect"))
    )
    (net (code "64") (name "unconnected-(U14-PB9-Pad46)") (class "Default")
      (node (ref "U14") (pin "46") (pinfunction "PB9_46") (pintype "bidirectional+no_connect"))
    )
    (net (code "65") (name "unconnected-(U14-PB10-Pad21)") (class "Default")
      (node (ref "U14") (pin "21") (pinfunction "PB10_21") (pintype "bidirectional+no_connect"))
    )
    (net (code "66") (name "unconnected-(U14-PB11-Pad22)") (class "Default")
      (node (ref "U14") (pin "22") (pinfunction "PB11_22") (pintype "bidirectional+no_connect"))
    )
    (net (code "67") (name "unconnected-(U14-PC15-Pad4)") (class "Default")
      (node (ref "U14") (pin "4") (pinfunction "PC15_4") (pintype "bidirectional+no_connect"))
    )
  )
)
